# RGB_Ring_v2_SCH.net
KiCad netlist of a schematic drawn in Altium Designer
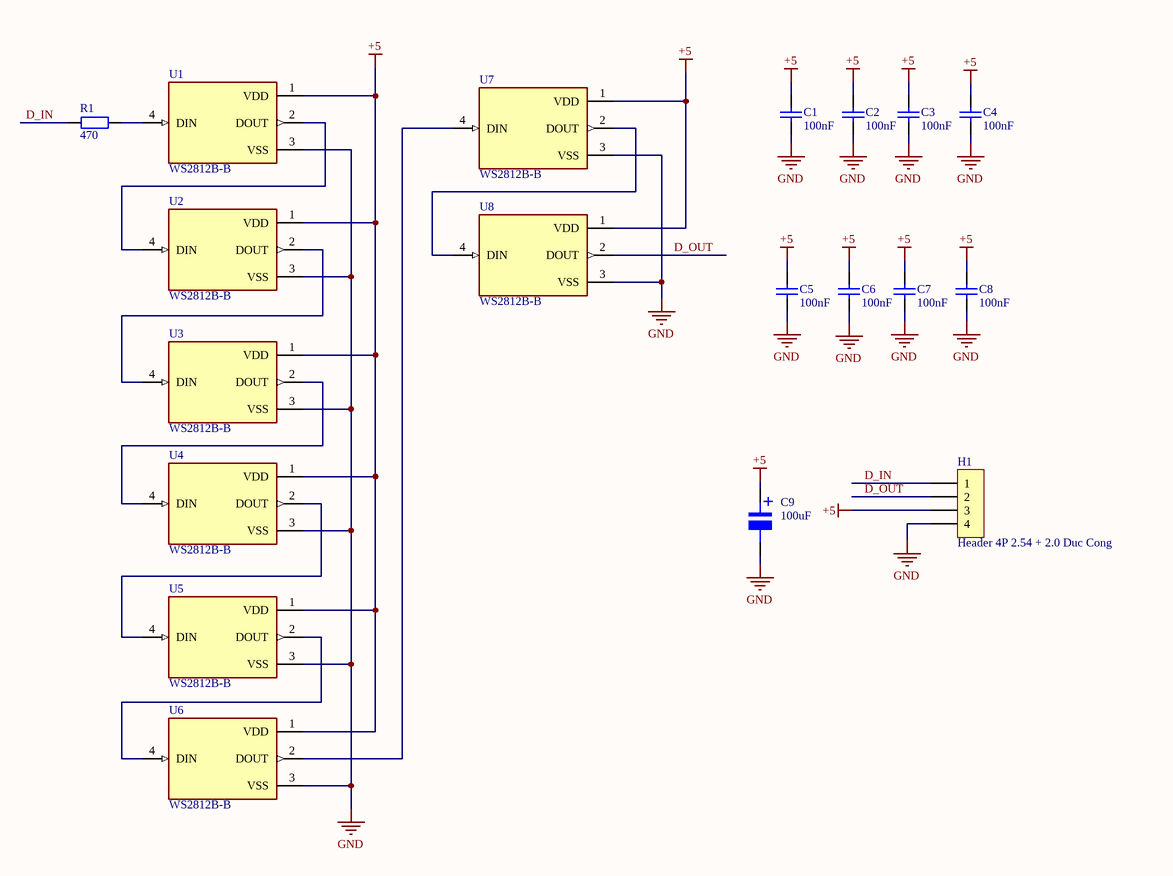
[diagram p0: RGB_Ring_v2_SCH.SchDoc]

(export (version "E")
  (design (tool "Eeschema 10.0.6"))
  (components
    (comp (ref "C1")
      (value "100nF")
      (footprint "tu 0603")
      (description "Dán")
      (libsource (lib "namnt_Lib") (part "Tu 0603 104 50V 10%"))
    )
    (comp (ref "C2")
      (value "100nF")
      (footprint "tu 0603")
      (description "Dán")
      (libsource (lib "namnt_Lib") (part "Tu 0603 104 50V 10%"))
    )
    (comp (ref "C3")
      (value "100nF")
      (footprint "tu 0603")
      (description "Dán")
      (libsource (lib "namnt_Lib") (part "Tu 0603 104 50V 10%"))
    )
    (comp (ref "C4")
      (value "100nF")
      (footprint "tu 0603")
      (description "Dán")
      (libsource (lib "namnt_Lib") (part "Tu 0603 104 50V 10%"))
    )
    (comp (ref "C5")
      (value "100nF")
      (footprint "tu 0603")
      (description "Dán")
      (libsource (lib "namnt_Lib") (part "Tu 0603 104 50V 10%"))
    )
    (comp (ref "C6")
      (value "100nF")
      (footprint "tu 0603")
      (description "Dán")
      (libsource (lib "namnt_Lib") (part "Tu 0603 104 50V 10%"))
    )
    (comp (ref "C7")
      (value "100nF")
      (footprint "tu 0603")
      (description "Dán")
      (libsource (lib "namnt_Lib") (part "Tu 0603 104 50V 10%"))
    )
    (comp (ref "C8")
      (value "100nF")
      (footprint "tu 0603")
      (description "Dán")
      (libsource (lib "namnt_Lib") (part "Tu 0603 104 50V 10%"))
    )
    (comp (ref "C9")
      (value "100uF")
      (footprint "tu nhom 6.3 (d)")
      (description "Dán")
      (libsource (lib "namnt_Lib") (part "Tu Nhom 100uF 16V"))
    )
    (comp (ref "H1")
      (value "Header 4P 2.54 + 2.0 Duc Cong")
      (footprint "Header 4P DC 2.54 + 2.0")
      (description "Cắm")
      (libsource (lib "namnt_Lib") (part "Header 4P 2.54 + 2.0 Duc Cong"))
    )
    (comp (ref "R1")
      (value "470")
      (footprint "tro smd 0603")
      (description "Dán")
      (libsource (lib "namnt_Lib") (part "Tro 0603 5% 470R"))
    )
    (comp (ref "U1")
      (value "WS2812B-B")
      (footprint "LED_WS2812B-B")
      (description "Intelligent control LED integrated light source")
      (libsource (lib "namnt_Lib") (part "WS2812B-B"))
    )
    (comp (ref "U2")
      (value "WS2812B-B")
      (footprint "LED_WS2812B-B")
      (description "Intelligent control LED integrated light source")
      (libsource (lib "namnt_Lib") (part "WS2812B-B"))
    )
    (comp (ref "U3")
      (value "WS2812B-B")
      (footprint "LED_WS2812B-B")
      (description "Intelligent control LED integrated light source")
      (libsource (lib "namnt_Lib") (part "WS2812B-B"))
    )
    (comp (ref "U4")
      (value "WS2812B-B")
      (footprint "LED_WS2812B-B")
      (description "Intelligent control LED integrated light source")
      (libsource (lib "namnt_Lib") (part "WS2812B-B"))
    )
    (comp (ref "U5")
      (value "WS2812B-B")
      (footprint "LED_WS2812B-B")
      (description "Intelligent control LED integrated light source")
      (libsource (lib "namnt_Lib") (part "WS2812B-B"))
    )
    (comp (ref "U6")
      (value "WS2812B-B")
      (footprint "LED_WS2812B-B")
      (description "Intelligent control LED integrated light source")
      (libsource (lib "namnt_Lib") (part "WS2812B-B"))
    )
    (comp (ref "U7")
      (value "WS2812B-B")
      (footprint "LED_WS2812B-B")
      (description "Intelligent control LED integrated light source")
      (libsource (lib "namnt_Lib") (part "WS2812B-B"))
    )
    (comp (ref "U8")
      (value "WS2812B-B")
      (footprint "LED_WS2812B-B")
      (description "Intelligent control LED integrated light source")
      (libsource (lib "namnt_Lib") (part "WS2812B-B"))
    )
  )
  (nets
    (net (code "1") (name "+5") (class "Default")
      (node (ref "C1") (pin "1") (pinfunction "1_1") (pintype "passive"))
      (node (ref "C2") (pin "1") (pinfunction "1_1") (pintype "passive"))
      (node (ref "C3") (pin "1") (pinfunction "1_1") (pintype "passive"))
      (node (ref "C4") (pin "1") (pinfunction "1_1") (pintype "passive"))
      (node (ref "C5") (pin "1") (pinfunction "1_1") (pintype "passive"))
      (node (ref "C6") (pin "1") (pinfunction "1_1") (pintype "passive"))
      (node (ref "C7") (pin "1") (pinfunction "1_1") (pintype "passive"))
      (node (ref "C8") (pin "1") (pinfunction "1_1") (pintype "passive"))
      (node (ref "C9") (pin "1") (pinfunction "1_1") (pintype "passive"))
      (node (ref "H1") (pin "3") (pinfunction "3_3") (pintype "passive"))
      (node (ref "U1") (pin "1") (pinfunction "VDD_1") (pintype "power_in"))
      (node (ref "U2") (pin "1") (pinfunction "VDD_1") (pintype "power_in"))
      (node (ref "U3") (pin "1") (pinfunction "VDD_1") (pintype "power_in"))
      (node (ref "U4") (pin "1") (pinfunction "VDD_1") (pintype "power_in"))
      (node (ref "U5") (pin "1") (pinfunction "VDD_1") (pintype "power_in"))
      (node (ref "U6") (pin "1") (pinfunction "VDD_1") (pintype "power_in"))
      (node (ref "U7") (pin "1") (pinfunction "VDD_1") (pintype "power_in"))
      (node (ref "U8") (pin "1") (pinfunction "VDD_1") (pintype "power_in"))
    )
    (net (code "2") (name "/D_IN") (class "Default")
      (node (ref "H1") (pin "1") (pinfunction "1_1") (pintype "passive"))
      (node (ref "R1") (pin "1") (pinfunction "1_1") (pintype "passive"))
    )
    (net (code "3") (name "/D_OUT") (class "Default")
      (node (ref "H1") (pin "2") (pinfunction "2_2") (pintype "passive"))
      (node (ref "U8") (pin "2") (pinfunction "DOUT_2") (pintype "output"))
    )
    (net (code "4") (name "GND") (class "Default")
      (node (ref "C1") (pin "2") (pinfunction "2_2") (pintype "passive"))
      (node (ref "C2") (pin "2") (pinfunction "2_2") (pintype "passive"))
      (node (ref "C3") (pin "2") (pinfunction "2_2") (pintype "passive"))
      (node (ref "C4") (pin "2") (pinfunction "2_2") (pintype "passive"))
      (node (ref "C5") (pin "2") (pinfunction "2_2") (pintype "passive"))
      (node (ref "C6") (pin "2") (pinfunction "2_2") (pintype "passive"))
      (node (ref "C7") (pin "2") (pinfunction "2_2") (pintype "passive"))
      (node (ref "C8") (pin "2") (pinfunction "2_2") (pintype "passive"))
      (node (ref "C9") (pin "2") (pinfunction "2_2") (pintype "passive"))
      (node (ref "H1") (pin "4") (pinfunction "4_4") (pintype "passive"))
      (node (ref "U1") (pin "3") (pinfunction "VSS_3") (pintype "power_in"))
      (node (ref "U2") (pin "3") (pinfunction "VSS_3") (pintype "power_in"))
      (node (ref "U3") (pin "3") (pinfunction "VSS_3") (pintype "power_in"))
      (node (ref "U4") (pin "3") (pinfunction "VSS_3") (pintype "power_in"))
      (node (ref "U5") (pin "3") (pinfunction "VSS_3") (pintype "power_in"))
      (node (ref "U6") (pin "3") (pinfunction "VSS_3") (pintype "power_in"))
      (node (ref "U7") (pin "3") (pinfunction "VSS_3") (pintype "power_in"))
      (node (ref "U8") (pin "3") (pinfunction "VSS_3") (pintype "power_in"))
    )
    (net (code "5") (name "Net-(U1-DIN)") (class "Default")
      (node (ref "R1") (pin "2") (pinfunction "2_2") (pintype "passive"))
      (node (ref "U1") (pin "4") (pinfunction "DIN_4") (pintype "input"))
    )
    (net (code "6") (name "Net-(U1-DOUT)") (class "Default")
      (node (ref "U1") (pin "2") (pinfunction "DOUT_2") (pintype "output"))
      (node (ref "U2") (pin "4") (pinfunction "DIN_4") (pintype "input"))
    )
    (net (code "7") (name "Net-(U2-DOUT)") (class "Default")
      (node (ref "U2") (pin "2") (pinfunction "DOUT_2") (pintype "output"))
      (node (ref "U3") (pin "4") (pinfunction "DIN_4") (pintype "input"))
    )
    (net (code "8") (name "Net-(U3-DOUT)") (class "Default")
      (node (ref "U3") (pin "2") (pinfunction "DOUT_2") (pintype "output"))
      (node (ref "U4") (pin "4") (pinfunction "DIN_4") (pintype "input"))
    )
    (net (code "9") (name "Net-(U4-DOUT)") (class "Default")
      (node (ref "U4") (pin "2") (pinfunction "DOUT_2") (pintype "output"))
      (node (ref "U5") (pin "4") (pinfunction "DIN_4") (pintype "input"))
    )
    (net (code "10") (name "Net-(U5-DOUT)") (class "Default")
      (node (ref "U5") (pin "2") (pinfunction "DOUT_2") (pintype "output"))
      (node (ref "U6") (pin "4") (pinfunction "DIN_4") (pintype "input"))
    )
    (net (code "11") (name "Net-(U6-DOUT)") (class "Default")
      (node (ref "U6") (pin "2") (pinfunction "DOUT_2") (pintype "output"))
      (node (ref "U7") (pin "4") (pinfunction "DIN_4") (pintype "input"))
    )
    (net (code "12") (name "Net-(U7-DOUT)") (class "Default")
      (node (ref "U7") (pin "2") (pinfunction "DOUT_2") (pintype "output"))
      (node (ref "U8") (pin "4") (pinfunction "DIN_4") (pintype "input"))
    )
  )
)
